# M707D.net
KiCad netlist of a schematic drawn in EAGLE
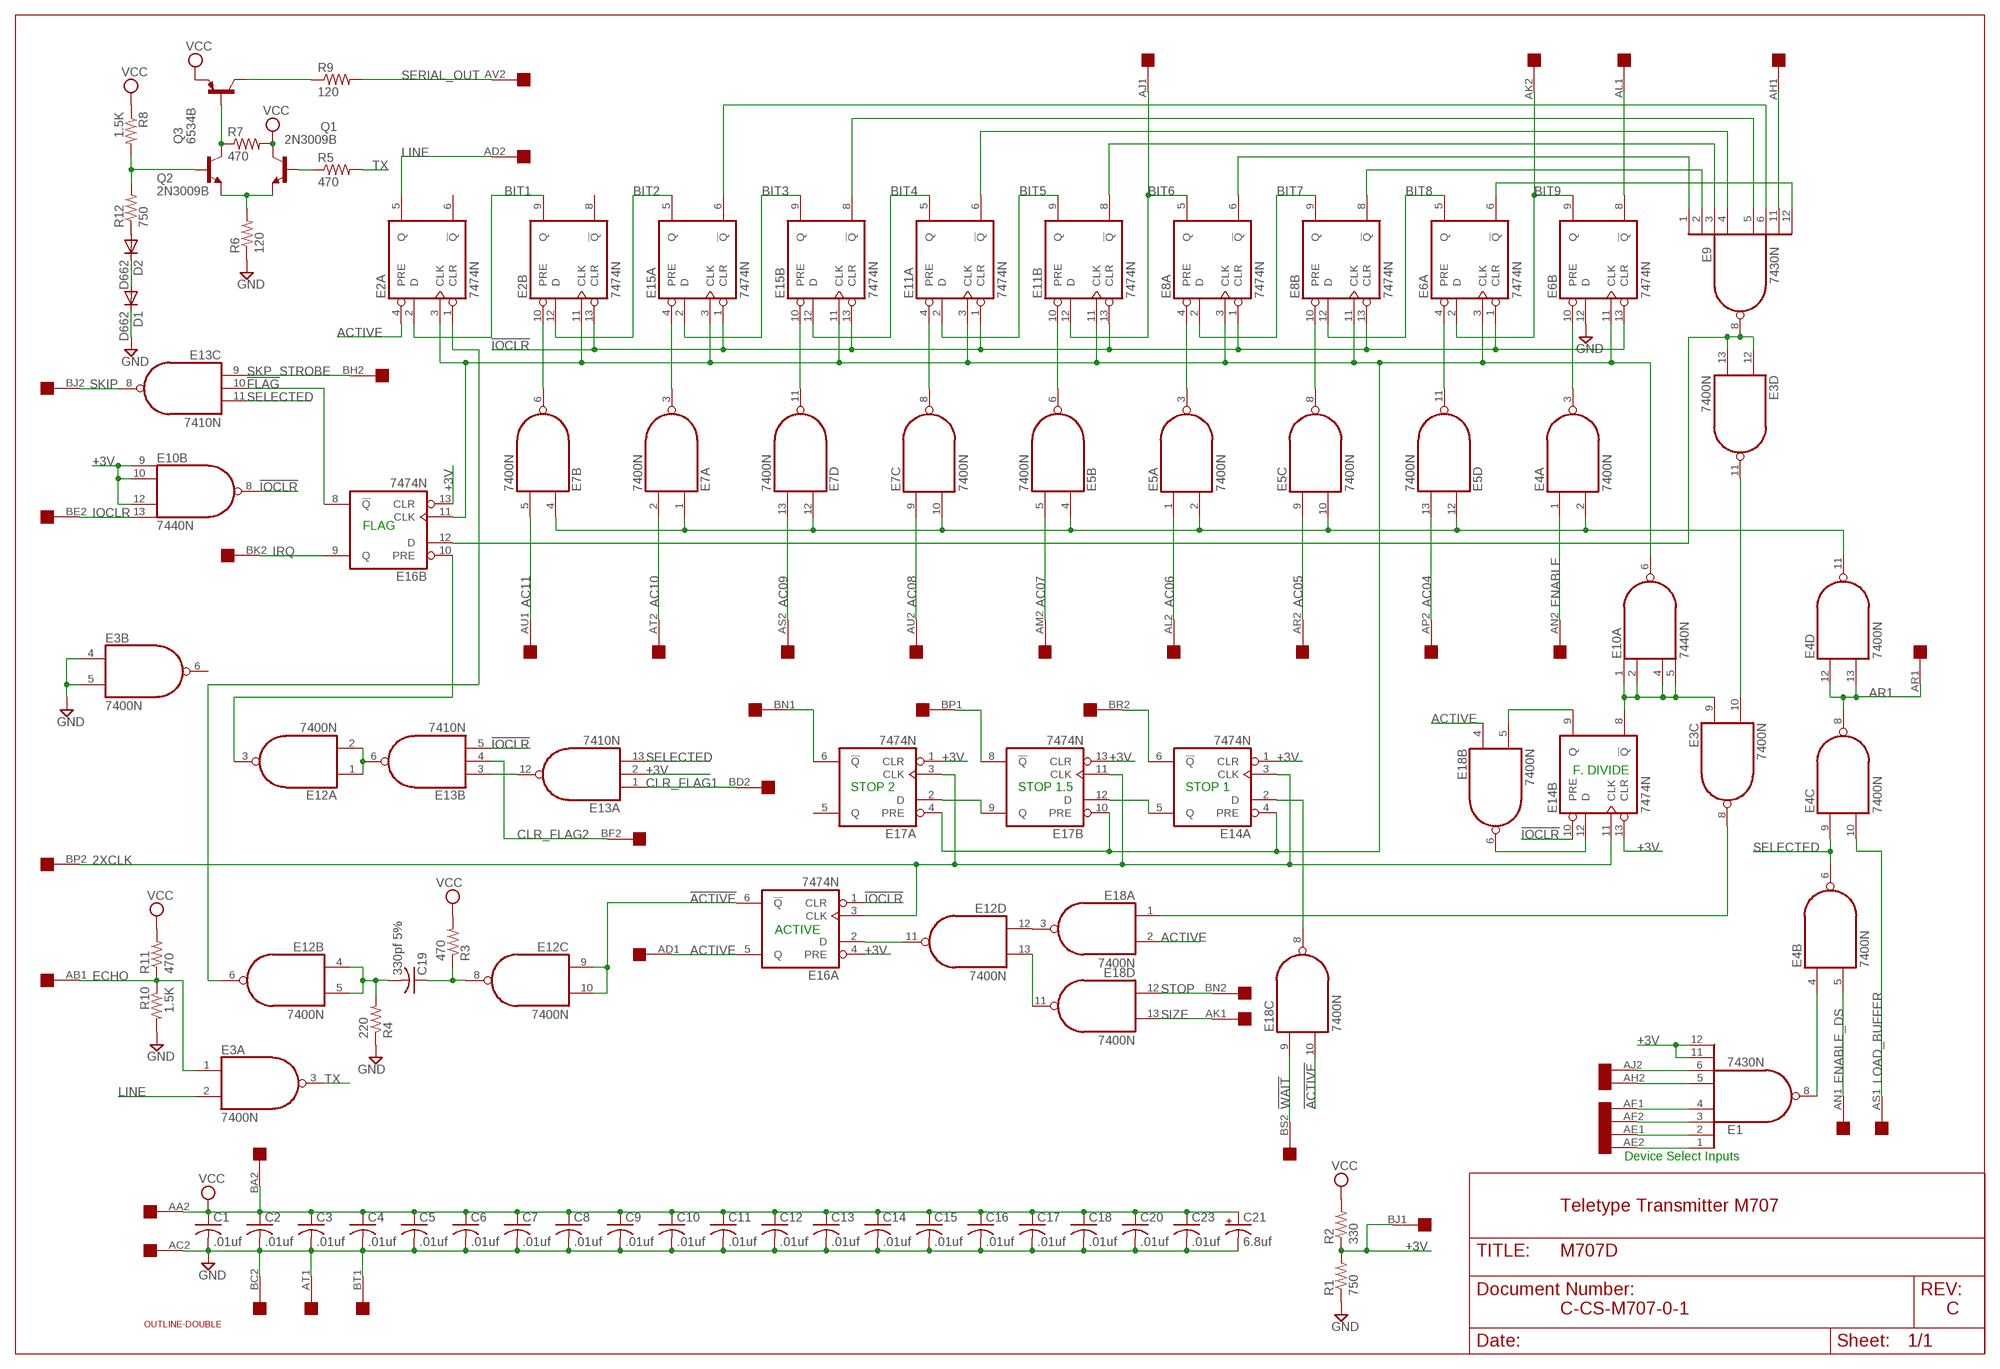
[diagram p0: schematic, sheet 1]

(export (version "E")
  (design (tool "Eeschema 10.0.6"))
  (components
    (comp (ref "C1")
      (value ".01uf")
      (footprint "eagle-import:C050-025X075")
      (libsource (lib "eagle-import") (part "C-US050-025X075"))
    )
    (comp (ref "C2")
      (value ".01uf")
      (footprint "eagle-import:C050-025X075")
      (libsource (lib "eagle-import") (part "C-US050-025X075"))
    )
    (comp (ref "C3")
      (value ".01uf")
      (footprint "eagle-import:C050-025X075")
      (libsource (lib "eagle-import") (part "C-US050-025X075"))
    )
    (comp (ref "C4")
      (value ".01uf")
      (footprint "eagle-import:C050-025X075")
      (libsource (lib "eagle-import") (part "C-US050-025X075"))
    )
    (comp (ref "C5")
      (value ".01uf")
      (footprint "eagle-import:C050-025X075")
      (libsource (lib "eagle-import") (part "C-US050-025X075"))
    )
    (comp (ref "C6")
      (value ".01uf")
      (footprint "eagle-import:C050-025X075")
      (libsource (lib "eagle-import") (part "C-US050-025X075"))
    )
    (comp (ref "C7")
      (value ".01uf")
      (footprint "eagle-import:C050-025X075")
      (libsource (lib "eagle-import") (part "C-US050-025X075"))
    )
    (comp (ref "C8")
      (value ".01uf")
      (footprint "eagle-import:C050-025X075")
      (libsource (lib "eagle-import") (part "C-US050-025X075"))
    )
    (comp (ref "C9")
      (value ".01uf")
      (footprint "eagle-import:C050-025X075")
      (libsource (lib "eagle-import") (part "C-US050-025X075"))
    )
    (comp (ref "C10")
      (value ".01uf")
      (footprint "eagle-import:C050-025X075")
      (libsource (lib "eagle-import") (part "C-US050-025X075"))
    )
    (comp (ref "C11")
      (value ".01uf")
      (footprint "eagle-import:C050-025X075")
      (libsource (lib "eagle-import") (part "C-US050-025X075"))
    )
    (comp (ref "C12")
      (value ".01uf")
      (footprint "eagle-import:C050-025X075")
      (libsource (lib "eagle-import") (part "C-US050-025X075"))
    )
    (comp (ref "C13")
      (value ".01uf")
      (footprint "eagle-import:C050-025X075")
      (libsource (lib "eagle-import") (part "C-US050-025X075"))
    )
    (comp (ref "C14")
      (value ".01uf")
      (footprint "eagle-import:C050-025X075")
      (libsource (lib "eagle-import") (part "C-US050-025X075"))
    )
    (comp (ref "C15")
      (value ".01uf")
      (footprint "eagle-import:C050-025X075")
      (libsource (lib "eagle-import") (part "C-US050-025X075"))
    )
    (comp (ref "C16")
      (value ".01uf")
      (footprint "eagle-import:C050-025X075")
      (libsource (lib "eagle-import") (part "C-US050-025X075"))
    )
    (comp (ref "C17")
      (value ".01uf")
      (footprint "eagle-import:C050-025X075")
      (libsource (lib "eagle-import") (part "C-US050-025X075"))
    )
    (comp (ref "C18")
      (value ".01uf")
      (footprint "eagle-import:C050-025X075")
      (libsource (lib "eagle-import") (part "C-US050-025X075"))
    )
    (comp (ref "C19")
      (value "330pf 5%")
      (footprint "eagle-import:C075-032X103")
      (libsource (lib "eagle-import") (part "C-US075-032X103"))
    )
    (comp (ref "C20")
      (value ".01uf")
      (footprint "eagle-import:C050-025X075")
      (libsource (lib "eagle-import") (part "C-US050-025X075"))
    )
    (comp (ref "C21")
      (value "6.8uf")
      (footprint "eagle-import:E15-5")
      (libsource (lib "eagle-import") (part "CPOL-USE15-5AXIAL"))
    )
    (comp (ref "C23")
      (value ".01uf")
      (footprint "eagle-import:C050-025X075")
      (libsource (lib "eagle-import") (part "C-US050-025X075"))
    )
    (comp (ref "D1")
      (value "D662")
      (footprint "eagle-import:DO35-10")
      (libsource (lib "eagle-import") (part "1N4148DO35-10"))
    )
    (comp (ref "D2")
      (value "D662")
      (footprint "eagle-import:DO35-10")
      (libsource (lib "eagle-import") (part "1N4148DO35-10"))
    )
    (comp (ref "E1")
      (value "7430N")
      (footprint "eagle-import:DIL14")
      (libsource (lib "eagle-import") (part "7430N"))
    )
    (comp (ref "E2")
      (value "7474N")
      (footprint "eagle-import:DIL14")
      (libsource (lib "eagle-import") (part "7474NS"))
    )
    (comp (ref "E3")
      (value "7400N")
      (footprint "eagle-import:DIL14")
      (libsource (lib "eagle-import") (part "7400N"))
    )
    (comp (ref "E4")
      (value "7400N")
      (footprint "eagle-import:DIL14")
      (libsource (lib "eagle-import") (part "7400N"))
    )
    (comp (ref "E5")
      (value "7400N")
      (footprint "eagle-import:DIL14")
      (libsource (lib "eagle-import") (part "7400N"))
    )
    (comp (ref "E6")
      (value "7474N")
      (footprint "eagle-import:DIL14")
      (libsource (lib "eagle-import") (part "7474NS"))
    )
    (comp (ref "E7")
      (value "7400N")
      (footprint "eagle-import:DIL14")
      (libsource (lib "eagle-import") (part "7400N"))
    )
    (comp (ref "E8")
      (value "7474N")
      (footprint "eagle-import:DIL14")
      (libsource (lib "eagle-import") (part "7474NS"))
    )
    (comp (ref "E9")
      (value "7430N")
      (footprint "eagle-import:DIL14")
      (libsource (lib "eagle-import") (part "7430N"))
    )
    (comp (ref "E10")
      (value "7440N")
      (footprint "eagle-import:DIL14")
      (libsource (lib "eagle-import") (part "7420NS"))
    )
    (comp (ref "E11")
      (value "7474N")
      (footprint "eagle-import:DIL14")
      (libsource (lib "eagle-import") (part "7474NS"))
    )
    (comp (ref "E12")
      (value "7400N")
      (footprint "eagle-import:DIL14")
      (libsource (lib "eagle-import") (part "7400N"))
    )
    (comp (ref "E13")
      (value "7410N")
      (footprint "eagle-import:DIL14")
      (libsource (lib "eagle-import") (part "7410N"))
    )
    (comp (ref "E14")
      (value "7474N")
      (footprint "eagle-import:DIL14")
      (libsource (lib "eagle-import") (part "7474NS"))
    )
    (comp (ref "E15")
      (value "7474N")
      (footprint "eagle-import:DIL14")
      (libsource (lib "eagle-import") (part "7474NS"))
    )
    (comp (ref "E16")
      (value "7474N")
      (footprint "eagle-import:DIL14")
      (libsource (lib "eagle-import") (part "7474NS"))
    )
    (comp (ref "E17")
      (value "7474N")
      (footprint "eagle-import:DIL14")
      (libsource (lib "eagle-import") (part "7474NS"))
    )
    (comp (ref "E18")
      (value "7400N")
      (footprint "eagle-import:DIL14")
      (libsource (lib "eagle-import") (part "7400N"))
    )
    (comp (ref "Q1")
      (value "2N3009B")
      (footprint "eagle-import:TO39")
      (libsource (lib "eagle-import") (part "-NPN-TO39-EBC2N3440"))
    )
    (comp (ref "Q2")
      (value "2N3009B")
      (footprint "eagle-import:TO39")
      (libsource (lib "eagle-import") (part "-NPN-TO39-EBC2N3440"))
    )
    (comp (ref "Q3")
      (value "6534B")
      (footprint "eagle-import:TO39")
      (libsource (lib "eagle-import") (part "-PNP-TO39-EBC2N3637"))
    )
    (comp (ref "R1")
      (value "750")
      (footprint "eagle-import:0207_10")
      (libsource (lib "eagle-import") (part "R-US_0207/10"))
    )
    (comp (ref "R2")
      (value "330")
      (footprint "eagle-import:0207_10")
      (libsource (lib "eagle-import") (part "R-US_0207/10"))
    )
    (comp (ref "R3")
      (value "470")
      (footprint "eagle-import:0207_10")
      (libsource (lib "eagle-import") (part "R-US_0207/10"))
    )
    (comp (ref "R4")
      (value "220")
      (footprint "eagle-import:0207_10")
      (libsource (lib "eagle-import") (part "R-US_0207/10"))
    )
    (comp (ref "R5")
      (value "470")
      (footprint "eagle-import:0207_10")
      (libsource (lib "eagle-import") (part "R-US_0207/10"))
    )
    (comp (ref "R6")
      (value "120")
      (footprint "eagle-import:0207_10")
      (libsource (lib "eagle-import") (part "R-US_0207/10"))
    )
    (comp (ref "R7")
      (value "470")
      (footprint "eagle-import:0207_10")
      (libsource (lib "eagle-import") (part "R-US_0207/10"))
    )
    (comp (ref "R8")
      (value "1.5K")
      (footprint "eagle-import:0207_10")
      (libsource (lib "eagle-import") (part "R-US_0207/10"))
    )
    (comp (ref "R9")
      (value "120")
      (footprint "eagle-import:0207_10")
      (libsource (lib "eagle-import") (part "R-US_0207/10"))
    )
    (comp (ref "R10")
      (value "1.5K")
      (footprint "eagle-import:0207_10")
      (libsource (lib "eagle-import") (part "R-US_0207/10"))
    )
    (comp (ref "R11")
      (value "470")
      (footprint "eagle-import:0207_10")
      (libsource (lib "eagle-import") (part "R-US_0207/10"))
    )
    (comp (ref "R12")
      (value "750")
      (footprint "eagle-import:0207_10")
      (libsource (lib "eagle-import") (part "R-US_0207/10"))
    )
    (comp (ref "U$1")
      (value "OUTLINE-DOUBLE")
      (footprint "eagle-import:DOUBLE")
      (libsource (lib "eagle-import") (part "OUTLINE-DOUBLE"))
    )
    (comp (ref "U$2")
      (value "DOUBLE")
      (footprint "eagle-import:EDGE-CON4")
      (libsource (lib "eagle-import") (part "DOUBLE"))
    )
  )
  (nets
    (net (code "1") (name "/+3V") (class "Default")
      (node (ref "E1") (pin "11") (pinfunction "I6_11") (pintype "input"))
      (node (ref "E1") (pin "12") (pinfunction "I7_12") (pintype "input"))
      (node (ref "E10") (pin "10") (pinfunction "I1_10") (pintype "input"))
      (node (ref "E10") (pin "12") (pinfunction "I2_12") (pintype "input"))
      (node (ref "E10") (pin "9") (pinfunction "I0_9") (pintype "input"))
      (node (ref "E13") (pin "2") (pinfunction "I1_2") (pintype "input"))
      (node (ref "E14") (pin "1") (pinfunction "CLR_1") (pintype "input"))
      (node (ref "E14") (pin "13") (pinfunction "CLR_13") (pintype "input"))
      (node (ref "E16") (pin "13") (pinfunction "CLR_13") (pintype "input"))
      (node (ref "E16") (pin "4") (pinfunction "PRE_4") (pintype "input"))
      (node (ref "E17") (pin "1") (pinfunction "CLR_1") (pintype "input"))
      (node (ref "E17") (pin "13") (pinfunction "CLR_13") (pintype "input"))
      (node (ref "R1") (pin "2") (pinfunction "2_2") (pintype "passive"))
      (node (ref "R2") (pin "1") (pinfunction "1_1") (pintype "passive"))
      (node (ref "U$2") (pin "BJ1") (pinfunction "1_BJ1") (pintype "bidirectional"))
    )
    (net (code "2") (name "/2XCLK") (class "Default")
      (node (ref "E14") (pin "11") (pinfunction "CLK_11") (pintype "input"))
      (node (ref "E14") (pin "3") (pinfunction "CLK_3") (pintype "input"))
      (node (ref "E16") (pin "3") (pinfunction "CLK_3") (pintype "input"))
      (node (ref "E17") (pin "11") (pinfunction "CLK_11") (pintype "input"))
      (node (ref "E17") (pin "3") (pinfunction "CLK_3") (pintype "input"))
      (node (ref "U$2") (pin "BP2") (pinfunction "1_BP2") (pintype "bidirectional"))
    )
    (net (code "3") (name "/AC04") (class "Default")
      (node (ref "E5") (pin "13") (pinfunction "I1_13") (pintype "input"))
      (node (ref "U$2") (pin "AP2") (pinfunction "1_AP2") (pintype "bidirectional"))
    )
    (net (code "4") (name "/AC05") (class "Default")
      (node (ref "E5") (pin "9") (pinfunction "I0_9") (pintype "input"))
      (node (ref "U$2") (pin "AR2") (pinfunction "1_AR2") (pintype "bidirectional"))
    )
    (net (code "5") (name "/AC06") (class "Default")
      (node (ref "E5") (pin "1") (pinfunction "I0_1") (pintype "input"))
      (node (ref "U$2") (pin "AL2") (pinfunction "1_AL2") (pintype "bidirectional"))
    )
    (net (code "6") (name "/AC07") (class "Default")
      (node (ref "E5") (pin "5") (pinfunction "I1_5") (pintype "input"))
      (node (ref "U$2") (pin "AM2") (pinfunction "1_AM2") (pintype "bidirectional"))
    )
    (net (code "7") (name "/AC08") (class "Default")
      (node (ref "E7") (pin "9") (pinfunction "I0_9") (pintype "input"))
      (node (ref "U$2") (pin "AU2") (pinfunction "1_AU2") (pintype "bidirectional"))
    )
    (net (code "8") (name "/AC09") (class "Default")
      (node (ref "E7") (pin "13") (pinfunction "I1_13") (pintype "input"))
      (node (ref "U$2") (pin "AS2") (pinfunction "1_AS2") (pintype "bidirectional"))
    )
    (net (code "9") (name "/AC10") (class "Default")
      (node (ref "E7") (pin "2") (pinfunction "I1_2") (pintype "input"))
      (node (ref "U$2") (pin "AT2") (pinfunction "1_AT2") (pintype "bidirectional"))
    )
    (net (code "10") (name "/AC11") (class "Default")
      (node (ref "E7") (pin "5") (pinfunction "I1_5") (pintype "input"))
      (node (ref "U$2") (pin "AU1") (pinfunction "1_AU1") (pintype "bidirectional"))
    )
    (net (code "11") (name "/ACTIVE") (class "Default")
      (node (ref "E16") (pin "5") (pinfunction "Q_5") (pintype "output"))
      (node (ref "E18") (pin "2") (pinfunction "I1_2") (pintype "input"))
      (node (ref "E18") (pin "4") (pinfunction "I0_4") (pintype "input"))
      (node (ref "E2") (pin "4") (pinfunction "PRE_4") (pintype "input"))
      (node (ref "U$2") (pin "AD1") (pinfunction "1_AD1") (pintype "bidirectional"))
    )
    (net (code "12") (name "/AR1") (class "Default")
      (node (ref "E4") (pin "12") (pinfunction "I0_12") (pintype "input"))
      (node (ref "E4") (pin "13") (pinfunction "I1_13") (pintype "input"))
      (node (ref "E4") (pin "8") (pinfunction "O_8") (pintype "output"))
      (node (ref "U$2") (pin "AR1") (pinfunction "1_AR1") (pintype "bidirectional"))
    )
    (net (code "13") (name "/BIT1") (class "Default")
      (node (ref "E2") (pin "2") (pinfunction "D_2") (pintype "input"))
      (node (ref "E2") (pin "9") (pinfunction "Q_9") (pintype "output"))
    )
    (net (code "14") (name "/BIT2") (class "Default")
      (node (ref "E15") (pin "5") (pinfunction "Q_5") (pintype "output"))
      (node (ref "E2") (pin "12") (pinfunction "D_12") (pintype "input"))
    )
    (net (code "15") (name "/BIT3") (class "Default")
      (node (ref "E15") (pin "2") (pinfunction "D_2") (pintype "input"))
      (node (ref "E15") (pin "9") (pinfunction "Q_9") (pintype "output"))
    )
    (net (code "16") (name "/BIT4") (class "Default")
      (node (ref "E11") (pin "5") (pinfunction "Q_5") (pintype "output"))
      (node (ref "E15") (pin "12") (pinfunction "D_12") (pintype "input"))
    )
    (net (code "17") (name "/BIT5") (class "Default")
      (node (ref "E11") (pin "2") (pinfunction "D_2") (pintype "input"))
      (node (ref "E11") (pin "9") (pinfunction "Q_9") (pintype "output"))
    )
    (net (code "18") (name "/BIT6") (class "Default")
      (node (ref "E11") (pin "12") (pinfunction "D_12") (pintype "input"))
      (node (ref "E8") (pin "5") (pinfunction "Q_5") (pintype "output"))
      (node (ref "U$2") (pin "AJ1") (pinfunction "1_AJ1") (pintype "bidirectional"))
    )
    (net (code "19") (name "/BIT7") (class "Default")
      (node (ref "E8") (pin "2") (pinfunction "D_2") (pintype "input"))
      (node (ref "E8") (pin "9") (pinfunction "Q_9") (pintype "output"))
    )
    (net (code "20") (name "/BIT8") (class "Default")
      (node (ref "E6") (pin "5") (pinfunction "Q_5") (pintype "output"))
      (node (ref "E8") (pin "12") (pinfunction "D_12") (pintype "input"))
    )
    (net (code "21") (name "/BIT9") (class "Default")
      (node (ref "E6") (pin "2") (pinfunction "D_2") (pintype "input"))
      (node (ref "E6") (pin "9") (pinfunction "Q_9") (pintype "output"))
      (node (ref "U$2") (pin "AK2") (pinfunction "1_AK2") (pintype "bidirectional"))
    )
    (net (code "22") (name "/CLR_FLAG1") (class "Default")
      (node (ref "E13") (pin "1") (pinfunction "I0_1") (pintype "input"))
      (node (ref "U$2") (pin "BD2") (pinfunction "1_BD2") (pintype "bidirectional"))
    )
    (net (code "23") (name "/CLR_FLAG2") (class "Default")
      (node (ref "E13") (pin "4") (pinfunction "I1_4") (pintype "input"))
      (node (ref "U$2") (pin "BF2") (pinfunction "1_BF2") (pintype "bidirectional"))
    )
    (net (code "24") (name "/ECHO") (class "Default")
      (node (ref "E3") (pin "1") (pinfunction "I0_1") (pintype "input"))
      (node (ref "R10") (pin "1") (pinfunction "1_1") (pintype "passive"))
      (node (ref "R11") (pin "1") (pinfunction "1_1") (pintype "passive"))
      (node (ref "U$2") (pin "AB1") (pinfunction "1_AB1") (pintype "bidirectional"))
    )
    (net (code "25") (name "/ENABLE") (class "Default")
      (node (ref "E4") (pin "1") (pinfunction "I0_1") (pintype "input"))
      (node (ref "U$2") (pin "AN2") (pinfunction "1_AN2") (pintype "bidirectional"))
    )
    (net (code "26") (name "/ENABLE_DS") (class "Default")
      (node (ref "E4") (pin "5") (pinfunction "I1_5") (pintype "input"))
      (node (ref "U$2") (pin "AN1") (pinfunction "1_AN1") (pintype "bidirectional"))
    )
    (net (code "27") (name "/IOCLR") (class "Default")
      (node (ref "E10") (pin "13") (pinfunction "I3_13") (pintype "input"))
      (node (ref "U$2") (pin "BE2") (pinfunction "1_BE2") (pintype "bidirectional"))
    )
    (net (code "28") (name "/IRQ") (class "Default")
      (node (ref "E16") (pin "9") (pinfunction "Q_9") (pintype "output"))
      (node (ref "U$2") (pin "BK2") (pinfunction "1_BK2") (pintype "bidirectional"))
    )
    (net (code "29") (name "/LINE") (class "Default")
      (node (ref "E2") (pin "5") (pinfunction "Q_5") (pintype "output"))
      (node (ref "E3") (pin "2") (pinfunction "I1_2") (pintype "input"))
      (node (ref "U$2") (pin "AD2") (pinfunction "1_AD2") (pintype "bidirectional"))
    )
    (net (code "30") (name "/LOAD_BUFFER") (class "Default")
      (node (ref "E4") (pin "10") (pinfunction "I1_10") (pintype "input"))
      (node (ref "U$2") (pin "AS1") (pinfunction "1_AS1") (pintype "bidirectional"))
    )
    (net (code "31") (name "/SELECTED") (class "Default")
      (node (ref "E13") (pin "11") (pinfunction "I2_11") (pintype "input"))
      (node (ref "E13") (pin "13") (pinfunction "I2_13") (pintype "input"))
      (node (ref "E4") (pin "6") (pinfunction "O_6") (pintype "output"))
      (node (ref "E4") (pin "9") (pinfunction "I0_9") (pintype "input"))
    )
    (net (code "32") (name "/SERIAL_OUT") (class "Default")
      (node (ref "R9") (pin "2") (pinfunction "2_2") (pintype "passive"))
      (node (ref "U$2") (pin "AV2") (pinfunction "1_AV2") (pintype "bidirectional"))
    )
    (net (code "33") (name "/SIZE") (class "Default")
      (node (ref "E18") (pin "13") (pinfunction "I1_13") (pintype "input"))
      (node (ref "U$2") (pin "AK1") (pinfunction "1_AK1") (pintype "bidirectional"))
    )
    (net (code "34") (name "/SKIP") (class "Default")
      (node (ref "E13") (pin "8") (pinfunction "O_8") (pintype "output"))
      (node (ref "U$2") (pin "BJ2") (pinfunction "1_BJ2") (pintype "bidirectional"))
    )
    (net (code "35") (name "/SKP_STROBE") (class "Default")
      (node (ref "E13") (pin "9") (pinfunction "I0_9") (pintype "input"))
      (node (ref "U$2") (pin "BH2") (pinfunction "1_BH2") (pintype "bidirectional"))
    )
    (net (code "36") (name "/STOP") (class "Default")
      (node (ref "E18") (pin "12") (pinfunction "I0_12") (pintype "input"))
      (node (ref "U$2") (pin "BN2") (pinfunction "1_BN2") (pintype "bidirectional"))
    )
    (net (code "37") (name "/TX") (class "Default")
      (node (ref "E3") (pin "3") (pinfunction "O_3") (pintype "output"))
      (node (ref "R5") (pin "2") (pinfunction "2_2") (pintype "passive"))
    )
    (net (code "38") (name "/~{ACTIVE}") (class "Default")
      (node (ref "E12") (pin "10") (pinfunction "I1_10") (pintype "input"))
      (node (ref "E12") (pin "9") (pinfunction "I0_9") (pintype "input"))
      (node (ref "E16") (pin "6") (pinfunction "~{Q}_6") (pintype "output"))
      (node (ref "E18") (pin "10") (pinfunction "I1_10") (pintype "input"))
    )
    (net (code "39") (name "/~{FLAG}") (class "Default")
      (node (ref "E13") (pin "10") (pinfunction "I1_10") (pintype "input"))
      (node (ref "E16") (pin "8") (pinfunction "~{Q}_8") (pintype "output"))
    )
    (net (code "40") (name "/~{IOCLR}") (class "Default")
      (node (ref "E10") (pin "8") (pinfunction "O_8") (pintype "output"))
      (node (ref "E11") (pin "1") (pinfunction "CLR_1") (pintype "input"))
      (node (ref "E11") (pin "13") (pinfunction "CLR_13") (pintype "input"))
      (node (ref "E13") (pin "5") (pinfunction "I2_5") (pintype "input"))
      (node (ref "E14") (pin "10") (pinfunction "PRE_10") (pintype "input"))
      (node (ref "E15") (pin "1") (pinfunction "CLR_1") (pintype "input"))
      (node (ref "E15") (pin "13") (pinfunction "CLR_13") (pintype "input"))
      (node (ref "E16") (pin "1") (pinfunction "CLR_1") (pintype "input"))
      (node (ref "E2") (pin "13") (pinfunction "CLR_13") (pintype "input"))
      (node (ref "E6") (pin "1") (pinfunction "CLR_1") (pintype "input"))
      (node (ref "E6") (pin "13") (pinfunction "CLR_13") (pintype "input"))
      (node (ref "E8") (pin "1") (pinfunction "CLR_1") (pintype "input"))
      (node (ref "E8") (pin "13") (pinfunction "CLR_13") (pintype "input"))
    )
    (net (code "41") (name "/~{WAIT}") (class "Default")
      (node (ref "E18") (pin "9") (pinfunction "I0_9") (pintype "input"))
      (node (ref "U$2") (pin "BS2") (pinfunction "1_BS2") (pintype "bidirectional"))
    )
    (net (code "42") (name "GND") (class "Default")
      (node (ref "C1") (pin "2") (pinfunction "2_2") (pintype "passive"))
      (node (ref "C10") (pin "2") (pinfunction "2_2") (pintype "passive"))
      (node (ref "C11") (pin "2") (pinfunction "2_2") (pintype "passive"))
      (node (ref "C12") (pin "2") (pinfunction "2_2") (pintype "passive"))
      (node (ref "C13") (pin "2") (pinfunction "2_2") (pintype "passive"))
      (node (ref "C14") (pin "2") (pinfunction "2_2") (pintype "passive"))
      (node (ref "C15") (pin "2") (pinfunction "2_2") (pintype "passive"))
      (node (ref "C16") (pin "2") (pinfunction "2_2") (pintype "passive"))
      (node (ref "C17") (pin "2") (pinfunction "2_2") (pintype "passive"))
      (node (ref "C18") (pin "2") (pinfunction "2_2") (pintype "passive"))
      (node (ref "C2") (pin "2") (pinfunction "2_2") (pintype "passive"))
      (node (ref "C20") (pin "2") (pinfunction "2_2") (pintype "passive"))
      (node (ref "C21") (pin "-") (pinfunction "-_-") (pintype "passive"))
      (node (ref "C23") (pin "2") (pinfunction "2_2") (pintype "passive"))
      (node (ref "C3") (pin "2") (pinfunction "2_2") (pintype "passive"))
      (node (ref "C4") (pin "2") (pinfunction "2_2") (pintype "passive"))
      (node (ref "C5") (pin "2") (pinfunction "2_2") (pintype "passive"))
      (node (ref "C6") (pin "2") (pinfunction "2_2") (pintype "passive"))
      (node (ref "C7") (pin "2") (pinfunction "2_2") (pintype "passive"))
      (node (ref "C8") (pin "2") (pinfunction "2_2") (pintype "passive"))
      (node (ref "C9") (pin "2") (pinfunction "2_2") (pintype "passive"))
      (node (ref "D1") (pin "C") (pinfunction "C_C") (pintype "passive"))
      (node (ref "E3") (pin "4") (pinfunction "I0_4") (pintype "input"))
      (node (ref "E3") (pin "5") (pinfunction "I1_5") (pintype "input"))
      (node (ref "E6") (pin "12") (pinfunction "D_12") (pintype "input"))
      (node (ref "R1") (pin "1") (pinfunction "1_1") (pintype "passive"))
      (node (ref "R10") (pin "2") (pinfunction "2_2") (pintype "passive"))
      (node (ref "R4") (pin "1") (pinfunction "1_1") (pintype "passive"))
      (node (ref "R6") (pin "1") (pinfunction "1_1") (pintype "passive"))
      (node (ref "U$2") (pin "AC2") (pinfunction "1_AC2") (pintype "bidirectional"))
      (node (ref "U$2") (pin "AT1") (pinfunction "1_AT1") (pintype "bidirectional"))
      (node (ref "U$2") (pin "BC2") (pinfunction "1_BC2") (pintype "bidirectional"))
      (node (ref "U$2") (pin "BT1") (pinfunction "1_BT1") (pintype "bidirectional"))
    )
    (net (code "43") (name "Net-(D1-PadA)") (class "Default")
      (node (ref "D1") (pin "A") (pinfunction "A_A") (pintype "passive"))
      (node (ref "D2") (pin "C") (pinfunction "C_C") (pintype "passive"))
    )
    (net (code "44") (name "Net-(D2-PadA)") (class "Default")
      (node (ref "D2") (pin "A") (pinfunction "A_A") (pintype "passive"))
      (node (ref "R12") (pin "1") (pinfunction "1_1") (pintype "passive"))
    )
    (net (code "45") (name "Net-(E1A-I0)") (class "Default")
      (node (ref "E1") (pin "1") (pinfunction "I0_1") (pintype "input"))
      (node (ref "U$2") (pin "AE2") (pinfunction "1_AE2") (pintype "bidirectional"))
    )
    (net (code "46") (name "Net-(E1A-I1)") (class "Default")
      (node (ref "E1") (pin "2") (pinfunction "I1_2") (pintype "input"))
      (node (ref "U$2") (pin "AE1") (pinfunction "1_AE1") (pintype "bidirectional"))
    )
    (net (code "47") (name "Net-(E1A-I2)") (class "Default")
      (node (ref "E1") (pin "3") (pinfunction "I2_3") (pintype "input"))
      (node (ref "U$2") (pin "AF2") (pinfunction "1_AF2") (pintype "bidirectional"))
    )
    (net (code "48") (name "Net-(E1A-I3)") (class "Default")
      (node (ref "E1") (pin "4") (pinfunction "I3_4") (pintype "input"))
      (node (ref "U$2") (pin "AF1") (pinfunction "1_AF1") (pintype "bidirectional"))
    )
    (net (code "49") (name "Net-(E1A-I4)") (class "Default")
      (node (ref "E1") (pin "5") (pinfunction "I4_5") (pintype "input"))
      (node (ref "U$2") (pin "AH2") (pinfunction "1_AH2") (pintype "bidirectional"))
    )
    (net (code "50") (name "Net-(E1A-I5)") (class "Default")
      (node (ref "E1") (pin "6") (pinfunction "I5_6") (pintype "input"))
      (node (ref "U$2") (pin "AJ2") (pinfunction "1_AJ2") (pintype "bidirectional"))
    )
    (net (code "51") (name "Net-(E1A-O)") (class "Default")
      (node (ref "E1") (pin "8") (pinfunction "O_8") (pintype "output"))
      (node (ref "E4") (pin "4") (pinfunction "I0_4") (pintype "input"))
    )
    (net (code "52") (name "Net-(E2B-PRE)") (class "Default")
      (node (ref "E2") (pin "10") (pinfunction "PRE_10") (pintype "input"))
      (node (ref "E7") (pin "6") (pinfunction "O_6") (pintype "output"))
    )
    (net (code "53") (name "Net-(E3C-I1)") (class "Default")
      (node (ref "E3") (pin "10") (pinfunction "I1_10") (pintype "input"))
      (node (ref "E3") (pin "11") (pinfunction "O_11") (pintype "output"))
    )
    (net (code "54") (name "Net-(E4A-I1)") (class "Default")
      (node (ref "E4") (pin "11") (pinfunction "O_11") (pintype "output"))
      (node (ref "E4") (pin "2") (pinfunction "I1_2") (pintype "input"))
      (node (ref "E5") (pin "10") (pinfunction "I1_10") (pintype "input"))
      (node (ref "E5") (pin "12") (pinfunction "I0_12") (pintype "input"))
      (node (ref "E5") (pin "2") (pinfunction "I1_2") (pintype "input"))
      (node (ref "E5") (pin "4") (pinfunction "I0_4") (pintype "input"))
      (node (ref "E7") (pin "1") (pinfunction "I0_1") (pintype "input"))
      (node (ref "E7") (pin "10") (pinfunction "I1_10") (pintype "input"))
      (node (ref "E7") (pin "12") (pinfunction "I0_12") (pintype "input"))
      (node (ref "E7") (pin "4") (pinfunction "I0_4") (pintype "input"))
    )
    (net (code "55") (name "Net-(E4A-O)") (class "Default")
      (node (ref "E4") (pin "3") (pinfunction "O_3") (pintype "output"))
      (node (ref "E6") (pin "10") (pinfunction "PRE_10") (pintype "input"))
    )
    (net (code "56") (name "Net-(E5A-O)") (class "Default")
      (node (ref "E5") (pin "3") (pinfunction "O_3") (pintype "output"))
      (node (ref "E8") (pin "4") (pinfunction "PRE_4") (pintype "input"))
    )
    (net (code "57") (name "Net-(E5C-O)") (class "Default")
      (node (ref "E5") (pin "8") (pinfunction "O_8") (pintype "output"))
      (node (ref "E8") (pin "10") (pinfunction "PRE_10") (pintype "input"))
    )
    (net (code "58") (name "Net-(E5D-O)") (class "Default")
      (node (ref "E5") (pin "11") (pinfunction "O_11") (pintype "output"))
      (node (ref "E6") (pin "4") (pinfunction "PRE_4") (pintype "input"))
    )
    (net (code "59") (name "Net-(E6A-~{Q})") (class "Default")
      (node (ref "E6") (pin "6") (pinfunction "~{Q}_6") (pintype "output"))
      (node (ref "E9") (pin "12") (pinfunction "I7_12") (pintype "input"))
    )
    (net (code "60") (name "Net-(E6B-~{Q})") (class "Default")
      (node (ref "E6") (pin "8") (pinfunction "~{Q}_8") (pintype "output"))
      (node (ref "U$2") (pin "AL1") (pinfunction "1_AL1") (pintype "bidirectional"))
    )
    (net (code "61") (name "Net-(E8A-~{Q})") (class "Default")
      (node (ref "E8") (pin "6") (pinfunction "~{Q}_6") (pintype "output"))
      (node (ref "E9") (pin "1") (pinfunction "I0_1") (pintype "input"))
    )
    (net (code "62") (name "Net-(E8B-~{Q})") (class "Default")
      (node (ref "E8") (pin "8") (pinfunction "~{Q}_8") (pintype "output"))
      (node (ref "E9") (pin "2") (pinfunction "I1_2") (pintype "input"))
    )
    (net (code "63") (name "Net-(E9A-I6)") (class "Default")
      (node (ref "E9") (pin "11") (pinfunction "I6_11") (pintype "input"))
      (node (ref "U$2") (pin "AH1") (pinfunction "1_AH1") (pintype "bidirectional"))
    )
    (net (code "64") (name "Net-(E10A-I0)") (class "Default")
      (node (ref "E10") (pin "1") (pinfunction "I0_1") (pintype "input"))
      (node (ref "E10") (pin "2") (pinfunction "I1_2") (pintype "input"))
      (node (ref "E10") (pin "4") (pinfunction "I2_4") (pintype "input"))
      (node (ref "E10") (pin "5") (pinfunction "I3_5") (pintype "input"))
      (node (ref "E14") (pin "8") (pinfunction "~{Q}_8") (pintype "output"))
      (node (ref "E3") (pin "9") (pinfunction "I0_9") (pintype "input"))
    )
    (net (code "65") (name "Net-(E10A-O)") (class "Default")
      (node (ref "E10") (pin "6") (pinfunction "O_6") (pintype "output"))
      (node (ref "E11") (pin "11") (pinfunction "CLK_11") (pintype "input"))
      (node (ref "E11") (pin "3") (pinfunction "CLK_3") (pintype "input"))
      (node (ref "E14") (pin "4") (pinfunction "PRE_4") (pintype "input"))
      (node (ref "E15") (pin "11") (pinfunction "CLK_11") (pintype "input"))
      (node (ref "E15") (pin "3") (pinfunction "CLK_3") (pintype "input"))
      (node (ref "E16") (pin "11") (pinfunction "CLK_11") (pintype "input"))
      (node (ref "E17") (pin "10") (pinfunction "PRE_10") (pintype "input"))
      (node (ref "E17") (pin "4") (pinfunction "PRE_4") (pintype "input"))
      (node (ref "E2") (pin "11") (pinfunction "CLK_11") (pintype "input"))
      (node (ref "E2") (pin "3") (pinfunction "CLK_3") (pintype "input"))
      (node (ref "E6") (pin "11") (pinfunction "CLK_11") (pintype "input"))
      (node (ref "E6") (pin "3") (pinfunction "CLK_3") (pintype "input"))
      (node (ref "E8") (pin "11") (pinfunction "CLK_11") (pintype "input"))
      (node (ref "E8") (pin "3") (pinfunction "CLK_3") (pintype "input"))
    )
    (net (code "66") (name "Net-(E11A-PRE)") (class "Default")
      (node (ref "E11") (pin "4") (pinfunction "PRE_4") (pintype "input"))
      (node (ref "E7") (pin "8") (pinfunction "O_8") (pintype "output"))
    )
    (net (code "67") (name "Net-(E11A-~{Q})") (class "Default")
      (node (ref "E11") (pin "6") (pinfunction "~{Q}_6") (pintype "output"))
      (node (ref "E9") (pin "4") (pinfunction "I3_4") (pintype "input"))
    )
    (net (code "68") (name "Net-(E11B-PRE)") (class "Default")
      (node (ref "E11") (pin "10") (pinfunction "PRE_10") (pintype "input"))
      (node (ref "E5") (pin "6") (pinfunction "O_6") (pintype "output"))
    )
    (net (code "69") (name "Net-(E11B-~{Q})") (class "Default")
      (node (ref "E11") (pin "8") (pinfunction "~{Q}_8") (pintype "output"))
      (node (ref "E9") (pin "3") (pinfunction "I2_3") (pintype "input"))
    )
    (net (code "70") (name "Net-(E12A-I0)") (class "Default")
      (node (ref "E12") (pin "1") (pinfunction "I0_1") (pintype "input"))
      (node (ref "E12") (pin "2") (pinfunction "I1_2") (pintype "input"))
      (node (ref "E13") (pin "6") (pinfunction "O_6") (pintype "output"))
    )
    (net (code "71") (name "Net-(E12A-O)") (class "Default")
      (node (ref "E12") (pin "3") (pinfunction "O_3") (pintype "output"))
      (node (ref "E16") (pin "10") (pinfunction "PRE_10") (pintype "input"))
    )
    (net (code "72") (name "Net-(E12B-I0)") (class "Default")
      (node (ref "C19") (pin "2") (pinfunction "2_2") (pintype "passive"))
      (node (ref "E12") (pin "4") (pinfunction "I0_4") (pintype "input"))
      (node (ref "E12") (pin "5") (pinfunction "I1_5") (pintype "input"))
      (node (ref "R4") (pin "2") (pinfunction "2_2") (pintype "passive"))
    )
    (net (code "73") (name "Net-(E12B-O)") (class "Default")
      (node (ref "E12") (pin "6") (pinfunction "O_6") (pintype "output"))
      (node (ref "E2") (pin "1") (pinfunction "CLR_1") (pintype "input"))
    )
    (net (code "74") (name "Net-(E12C-O)") (class "Default")
      (node (ref "C19") (pin "1") (pinfunction "1_1") (pintype "passive"))
      (node (ref "E12") (pin "8") (pinfunction "O_8") (pintype "output"))
      (node (ref "R3") (pin "1") (pinfunction "1_1") (pintype "passive"))
    )
    (net (code "75") (name "Net-(E12D-I0)") (class "Default")
      (node (ref "E12") (pin "12") (pinfunction "I0_12") (pintype "input"))
      (node (ref "E18") (pin "3") (pinfunction "O_3") (pintype "output"))
    )
    (net (code "76") (name "Net-(E12D-I1)") (class "Default")
      (node (ref "E12") (pin "13") (pinfunction "I1_13") (pintype "input"))
      (node (ref "E18") (pin "11") (pinfunction "O_11") (pintype "output"))
    )
    (net (code "77") (name "Net-(E12D-O)") (class "Default")
      (node (ref "E12") (pin "11") (pinfunction "O_11") (pintype "output"))
      (node (ref "E16") (pin "2") (pinfunction "D_2") (pintype "input"))
    )
    (net (code "78") (name "Net-(E13A-O)") (class "Default")
      (node (ref "E13") (pin "12") (pinfunction "O_12") (pintype "output"))
      (node (ref "E13") (pin "3") (pinfunction "I0_3") (pintype "input"))
    )
    (net (code "79") (name "Net-(E14A-D)") (class "Default")
      (node (ref "E14") (pin "2") (pinfunction "D_2") (pintype "input"))
      (node (ref "E18") (pin "8") (pinfunction "O_8") (pintype "output"))
    )
    (net (code "80") (name "Net-(E14A-Q)") (class "Default")
      (node (ref "E14") (pin "5") (pinfunction "Q_5") (pintype "output"))
      (node (ref "E17") (pin "12") (pinfunction "D_12") (pintype "input"))
    )
    (net (code "81") (name "Net-(E14A-~{Q})") (class "Default")
      (node (ref "E14") (pin "6") (pinfunction "~{Q}_6") (pintype "output"))
      (node (ref "U$2") (pin "BR2") (pinfunction "1_BR2") (pintype "bidirectional"))
    )
    (net (code "82") (name "Net-(E14B-D)") (class "Default")
      (node (ref "E14") (pin "12") (pinfunction "D_12") (pintype "input"))
      (node (ref "E18") (pin "6") (pinfunction "O_6") (pintype "output"))
    )
    (net (code "83") (name "Net-(E14B-Q)") (class "Default")
      (node (ref "E14") (pin "9") (pinfunction "Q_9") (pintype "output"))
      (node (ref "E18") (pin "5") (pinfunction "I1_5") (pintype "input"))
    )
    (net (code "84") (name "Net-(E15A-PRE)") (class "Default")
      (node (ref "E15") (pin "4") (pinfunction "PRE_4") (pintype "input"))
      (node (ref "E7") (pin "3") (pinfunction "O_3") (pintype "output"))
    )
    (net (code "85") (name "Net-(E15A-~{Q})") (class "Default")
      (node (ref "E15") (pin "6") (pinfunction "~{Q}_6") (pintype "output"))
      (node (ref "E9") (pin "6") (pinfunction "I5_6") (pintype "input"))
    )
    (net (code "86") (name "Net-(E15B-PRE)") (class "Default")
      (node (ref "E15") (pin "10") (pinfunction "PRE_10") (pintype "input"))
      (node (ref "E7") (pin "11") (pinfunction "O_11") (pintype "output"))
    )
    (net (code "87") (name "Net-(E15B-~{Q})") (class "Default")
      (node (ref "E15") (pin "8") (pinfunction "~{Q}_8") (pintype "output"))
      (node (ref "E9") (pin "5") (pinfunction "I4_5") (pintype "input"))
    )
    (net (code "88") (name "Net-(E16B-D)") (class "Default")
      (node (ref "E16") (pin "12") (pinfunction "D_12") (pintype "input"))
      (node (ref "E3") (pin "12") (pinfunction "I0_12") (pintype "input"))
      (node (ref "E3") (pin "13") (pinfunction "I1_13") (pintype "input"))
      (node (ref "E9") (pin "8") (pinfunction "O_8") (pintype "output"))
    )
    (net (code "89") (name "Net-(E17A-D)") (class "Default")
      (node (ref "E17") (pin "2") (pinfunction "D_2") (pintype "input"))
      (node (ref "E17") (pin "9") (pinfunction "Q_9") (pintype "output"))
    )
    (net (code "90") (name "Net-(E17A-~{Q})") (class "Default")
      (node (ref "E17") (pin "6") (pinfunction "~{Q}_6") (pintype "output"))
      (node (ref "U$2") (pin "BN1") (pinfunction "1_BN1") (pintype "bidirectional"))
    )
    (net (code "91") (name "Net-(E17B-~{Q})") (class "Default")
      (node (ref "E17") (pin "8") (pinfunction "~{Q}_8") (pintype "output"))
      (node (ref "U$2") (pin "BP1") (pinfunction "1_BP1") (pintype "bidirectional"))
    )
    (net (code "92") (name "Net-(E18A-I0)") (class "Default")
      (node (ref "E18") (pin "1") (pinfunction "I0_1") (pintype "input"))
      (node (ref "E3") (pin "8") (pinfunction "O_8") (pintype "output"))
    )
    (net (code "93") (name "Net-(Q1-B)") (class "Default")
      (node (ref "Q1") (pin "2") (pinfunction "B_2") (pintype "passive"))
      (node (ref "R5") (pin "1") (pinfunction "1_1") (pintype "passive"))
    )
    (net (code "94") (name "Net-(Q1-E)") (class "Default")
      (node (ref "Q1") (pin "1") (pinfunction "E_1") (pintype "passive"))
      (node (ref "Q2") (pin "1") (pinfunction "E_1") (pintype "passive"))
      (node (ref "R6") (pin "2") (pinfunction "2_2") (pintype "passive"))
    )
    (net (code "95") (name "Net-(Q2-B)") (class "Default")
      (node (ref "Q2") (pin "2") (pinfunction "B_2") (pintype "passive"))
      (node (ref "R12") (pin "2") (pinfunction "2_2") (pintype "passive"))
      (node (ref "R8") (pin "2") (pinfunction "2_2") (pintype "passive"))
    )
    (net (code "96") (name "Net-(Q2-C)") (class "Default")
      (node (ref "Q2") (pin "3") (pinfunction "C_3") (pintype "passive"))
      (node (ref "Q3") (pin "2") (pinfunction "B_2") (pintype "passive"))
      (node (ref "R7") (pin "1") (pinfunction "1_1") (pintype "passive"))
    )
    (net (code "97") (name "Net-(Q3-C)") (class "Default")
      (node (ref "Q3") (pin "3") (pinfunction "C_3") (pintype "passive"))
      (node (ref "R9") (pin "1") (pinfunction "1_1") (pintype "passive"))
    )
    (net (code "98") (name "VCC") (class "Default")
      (node (ref "C1") (pin "1") (pinfunction "1_1") (pintype "passive"))
      (node (ref "C10") (pin "1") (pinfunction "1_1") (pintype "passive"))
      (node (ref "C11") (pin "1") (pinfunction "1_1") (pintype "passive"))
      (node (ref "C12") (pin "1") (pinfunction "1_1") (pintype "passive"))
      (node (ref "C13") (pin "1") (pinfunction "1_1") (pintype "passive"))
      (node (ref "C14") (pin "1") (pinfunction "1_1") (pintype "passive"))
      (node (ref "C15") (pin "1") (pinfunction "1_1") (pintype "passive"))
      (node (ref "C16") (pin "1") (pinfunction "1_1") (pintype "passive"))
      (node (ref "C17") (pin "1") (pinfunction "1_1") (pintype "passive"))
      (node (ref "C18") (pin "1") (pinfunction "1_1") (pintype "passive"))
      (node (ref "C2") (pin "1") (pinfunction "1_1") (pintype "passive"))
      (node (ref "C20") (pin "1") (pinfunction "1_1") (pintype "passive"))
      (node (ref "C21") (pin "+") (pinfunction "+_+") (pintype "passive"))
      (node (ref "C23") (pin "1") (pinfunction "1_1") (pintype "passive"))
      (node (ref "C3") (pin "1") (pinfunction "1_1") (pintype "passive"))
      (node (ref "C4") (pin "1") (pinfunction "1_1") (pintype "passive"))
      (node (ref "C5") (pin "1") (pinfunction "1_1") (pintype "passive"))
      (node (ref "C6") (pin "1") (pinfunction "1_1") (pintype "passive"))
      (node (ref "C7") (pin "1") (pinfunction "1_1") (pintype "passive"))
      (node (ref "C8") (pin "1") (pinfunction "1_1") (pintype "passive"))
      (node (ref "C9") (pin "1") (pinfunction "1_1") (pintype "passive"))
      (node (ref "Q1") (pin "3") (pinfunction "C_3") (pintype "passive"))
      (node (ref "Q3") (pin "1") (pinfunction "E_1") (pintype "passive"))
      (node (ref "R11") (pin "2") (pinfunction "2_2") (pintype "passive"))
      (node (ref "R2") (pin "2") (pinfunction "2_2") (pintype "passive"))
      (node (ref "R3") (pin "2") (pinfunction "2_2") (pintype "passive"))
      (node (ref "R7") (pin "2") (pinfunction "2_2") (pintype "passive"))
      (node (ref "R8") (pin "1") (pinfunction "1_1") (pintype "passive"))
      (node (ref "U$2") (pin "AA2") (pinfunction "1_AA2") (pintype "bidirectional"))
      (node (ref "U$2") (pin "BA2") (pinfunction "1_BA2") (pintype "bidirectional"))
    )
    (net (code "99") (name "unconnected-(E2A-~{Q}-Pad6)") (class "Default")
      (node (ref "E2") (pin "6") (pinfunction "~{Q}_6") (pintype "output"))
    )
    (net (code "100") (name "unconnected-(E2B-~{Q}-Pad8)") (class "Default")
      (node (ref "E2") (pin "8") (pinfunction "~{Q}_8") (pintype "output"))
    )
    (net (code "101") (name "unconnected-(E3B-O-Pad6)") (class "Default")
      (node (ref "E3") (pin "6") (pinfunction "O_6") (pintype "output"))
    )
    (net (code "102") (name "unconnected-(E17A-Q-Pad5)") (class "Default")
      (node (ref "E17") (pin "5") (pinfunction "Q_5") (pintype "output"))
    )
  )
)
